# esp32Layout1.net
KiCad netlist of a schematic drawn in EAGLE
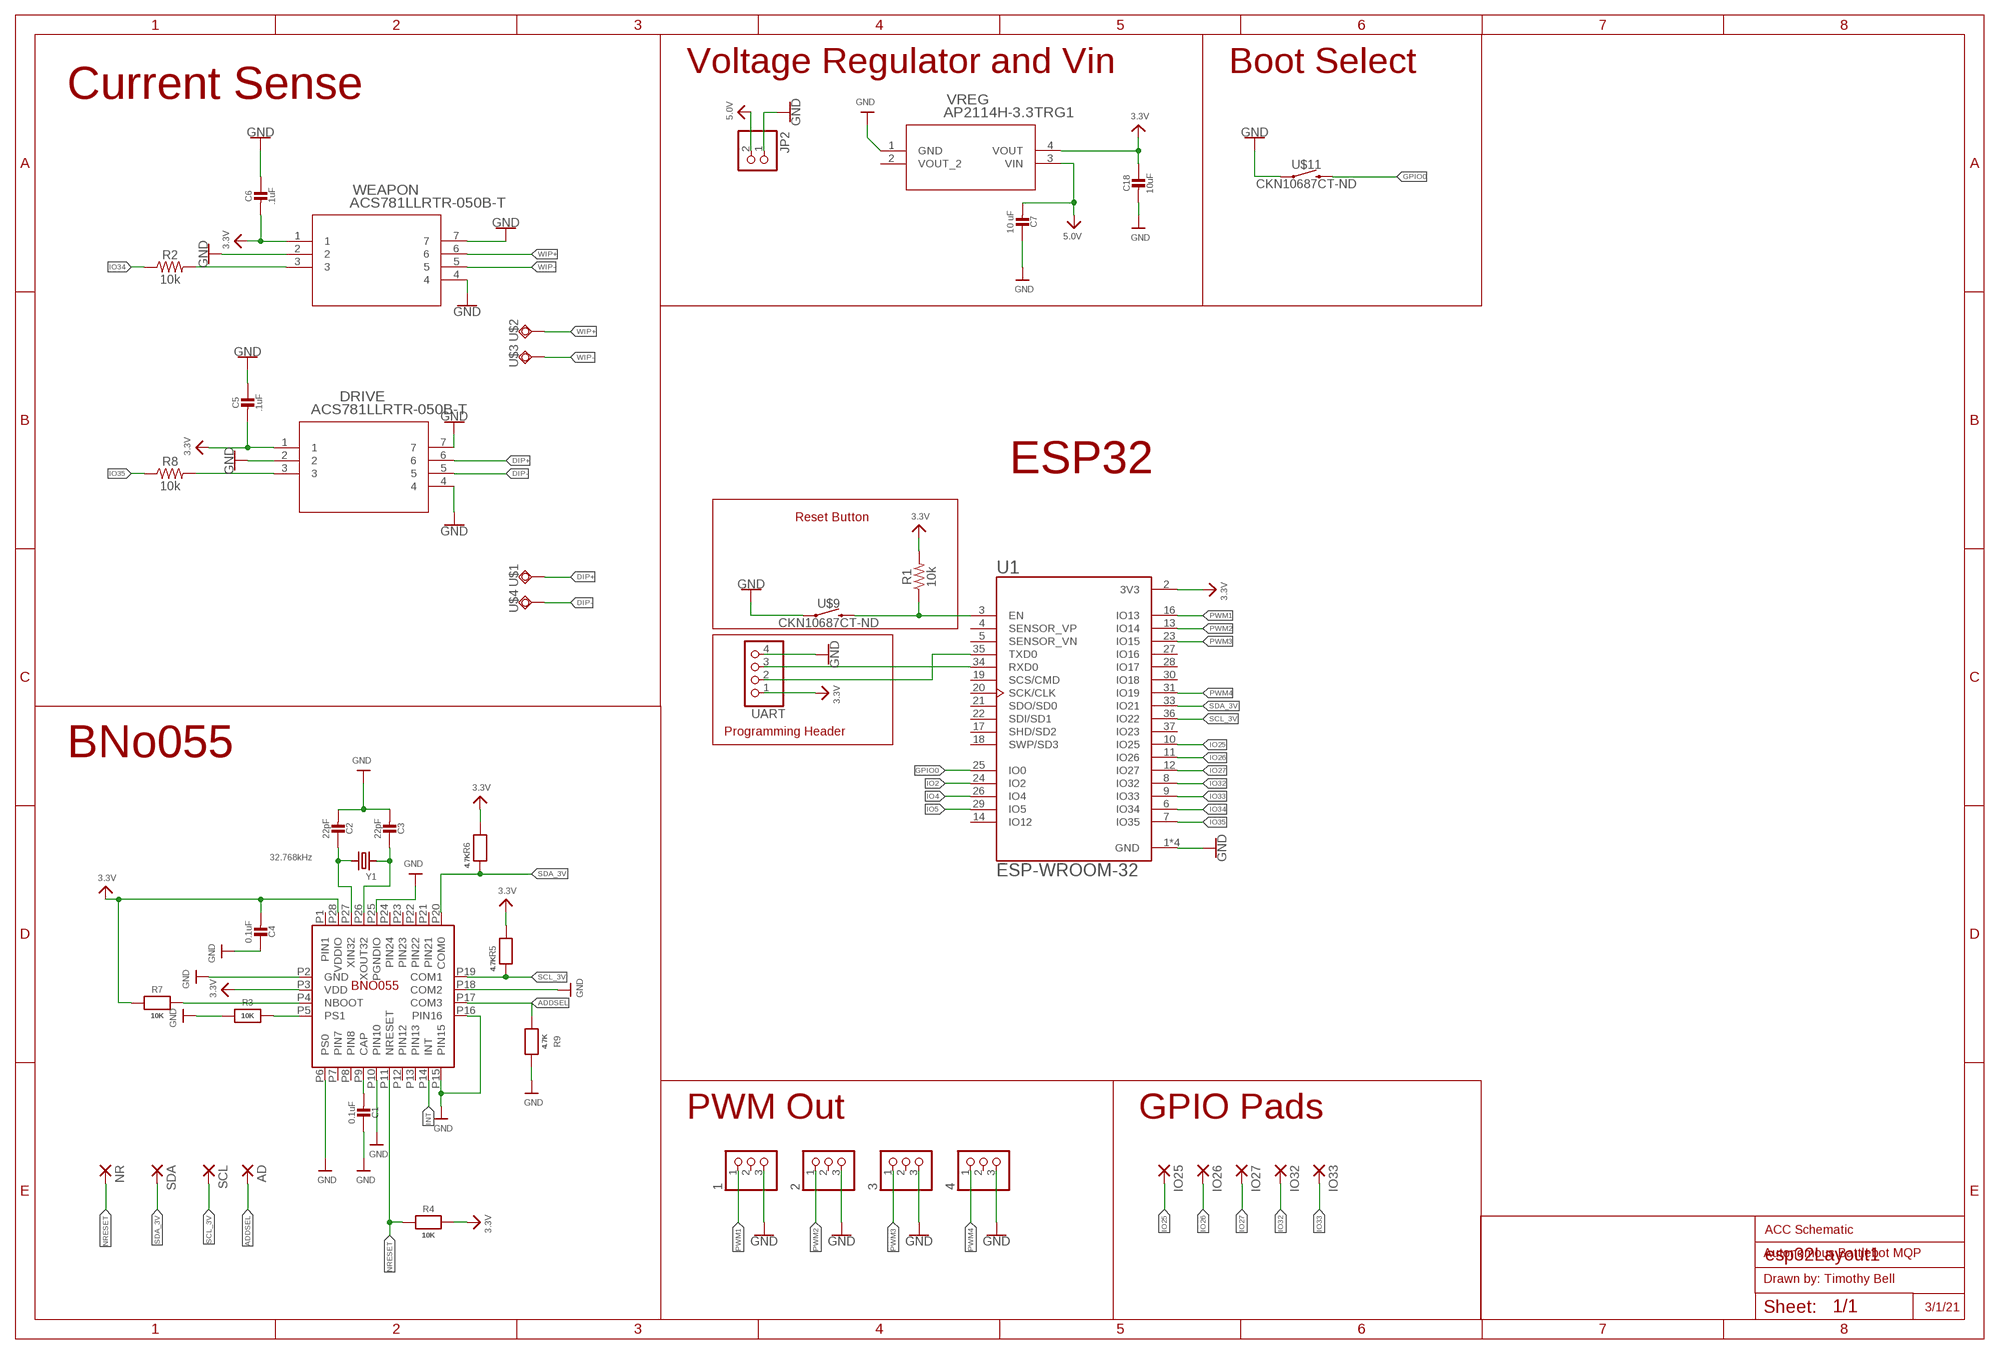
[diagram p0: schematic, sheet 1]

(export (version "E")
  (design (tool "Eeschema 10.0.6"))
  (components
    (comp (ref "1")
      (value "PINHD-1X3")
      (footprint "eagle-import:1X03")
      (libsource (lib "eagle-import") (part "PINHD-1X3"))
    )
    (comp (ref "2")
      (value "PINHD-1X3")
      (footprint "eagle-import:1X03")
      (libsource (lib "eagle-import") (part "PINHD-1X3"))
    )
    (comp (ref "3")
      (value "PINHD-1X3")
      (footprint "eagle-import:1X03")
      (libsource (lib "eagle-import") (part "PINHD-1X3"))
    )
    (comp (ref "4")
      (value "PINHD-1X3")
      (footprint "eagle-import:1X03")
      (libsource (lib "eagle-import") (part "PINHD-1X3"))
    )
    (comp (ref "AD")
      (value "SMD2")
      (footprint "eagle-import:SMD1,27-2,54")
      (libsource (lib "eagle-import") (part "SMD2"))
    )
    (comp (ref "BNO055")
      (value "BNO055")
      (footprint "eagle-import:BNO055")
      (libsource (lib "eagle-import") (part "BNO055"))
    )
    (comp (ref "C1")
      (value "0.1uF")
      (footprint "eagle-import:0805-NO")
      (libsource (lib "eagle-import") (part "CAP_CERAMIC0805-NOOUTLINE"))
    )
    (comp (ref "C2")
      (value "22pF")
      (footprint "eagle-import:0805-NO")
      (libsource (lib "eagle-import") (part "CAP_CERAMIC0805-NOOUTLINE"))
    )
    (comp (ref "C3")
      (value "22pF")
      (footprint "eagle-import:0805-NO")
      (libsource (lib "eagle-import") (part "CAP_CERAMIC0805-NOOUTLINE"))
    )
    (comp (ref "C4")
      (value "0.1uF")
      (footprint "eagle-import:0805-NO")
      (libsource (lib "eagle-import") (part "CAP_CERAMIC0805-NOOUTLINE"))
    )
    (comp (ref "C5")
      (value ".1uF")
      (footprint "eagle-import:0805_10MGAP")
      (libsource (lib "eagle-import") (part "CAP_CERAMIC0805_10MGAP"))
    )
    (comp (ref "C6")
      (value ".1uF")
      (footprint "eagle-import:0805_10MGAP")
      (libsource (lib "eagle-import") (part "CAP_CERAMIC0805_10MGAP"))
    )
    (comp (ref "C7")
      (value "10 uF")
      (footprint "eagle-import:0805-NO")
      (libsource (lib "eagle-import") (part "CAP_CERAMIC0805-NOOUTLINE"))
    )
    (comp (ref "C18")
      (value "10uF")
      (footprint "eagle-import:0805_10MGAP")
      (libsource (lib "eagle-import") (part "CAP_CERAMIC0805_10MGAP"))
    )
    (comp (ref "DRIVE")
      (value "ACS781LLRTR-050B-T")
      (footprint "eagle-import:PSOF7_ACS781LLRTR-050B-T_ALM")
      (fields (field (name "COPYRIGHT") "Copyright (C) 2018 Accelerated Designs. All rights reserved"))
      (libsource (lib "eagle-import") (part "ACS781LLRTR-050B-T"))
    )
    (comp (ref "IO25")
      (value "SMD2")
      (footprint "eagle-import:SMD1,27-2,54")
      (libsource (lib "eagle-import") (part "SMD2"))
    )
    (comp (ref "IO26")
      (value "SMD2")
      (footprint "eagle-import:SMD1,27-2,54")
      (libsource (lib "eagle-import") (part "SMD2"))
    )
    (comp (ref "IO27")
      (value "SMD2")
      (footprint "eagle-import:SMD1,27-2,54")
      (libsource (lib "eagle-import") (part "SMD2"))
    )
    (comp (ref "IO32")
      (value "SMD2")
      (footprint "eagle-import:SMD1,27-2,54")
      (libsource (lib "eagle-import") (part "SMD2"))
    )
    (comp (ref "IO33")
      (value "SMD2")
      (footprint "eagle-import:SMD1,27-2,54")
      (libsource (lib "eagle-import") (part "SMD2"))
    )
    (comp (ref "JP2")
      (value "PINHD-1X2")
      (footprint "eagle-import:1X02")
      (libsource (lib "eagle-import") (part "PINHD-1X2"))
    )
    (comp (ref "NR")
      (value "SMD2")
      (footprint "eagle-import:SMD1,27-2,54")
      (libsource (lib "eagle-import") (part "SMD2"))
    )
    (comp (ref "R1")
      (value "10k")
      (footprint "eagle-import:0603")
      (libsource (lib "eagle-import") (part "10KOHM-0603-1/10W-1%"))
    )
    (comp (ref "R2")
      (value "10k")
      (footprint "eagle-import:0603")
      (libsource (lib "eagle-import") (part "10KOHM-0603-1/10W-1%"))
    )
    (comp (ref "R3")
      (value "10K")
      (footprint "eagle-import:0805-NO")
      (libsource (lib "eagle-import") (part "RESISTOR0805_NOOUTLINE"))
    )
    (comp (ref "R4")
      (value "10K")
      (footprint "eagle-import:0805-NO")
      (libsource (lib "eagle-import") (part "RESISTOR0805_NOOUTLINE"))
    )
    (comp (ref "R5")
      (value "4.7K")
      (footprint "eagle-import:0805-NO")
      (libsource (lib "eagle-import") (part "RESISTOR0805_NOOUTLINE"))
    )
    (comp (ref "R6")
      (value "4.7K")
      (footprint "eagle-import:0805-NO")
      (libsource (lib "eagle-import") (part "RESISTOR0805_NOOUTLINE"))
    )
    (comp (ref "R7")
      (value "10K")
      (footprint "eagle-import:0805-NO")
      (libsource (lib "eagle-import") (part "RESISTOR0805_NOOUTLINE"))
    )
    (comp (ref "R8")
      (value "10k")
      (footprint "eagle-import:0603")
      (libsource (lib "eagle-import") (part "10KOHM-0603-1/10W-1%"))
    )
    (comp (ref "R9")
      (value "4.7K")
      (footprint "eagle-import:0805-NO")
      (libsource (lib "eagle-import") (part "RESISTOR0805_NOOUTLINE"))
    )
    (comp (ref "SCL")
      (value "SMD2")
      (footprint "eagle-import:SMD1,27-2,54")
      (libsource (lib "eagle-import") (part "SMD2"))
    )
    (comp (ref "SDA")
      (value "SMD2")
      (footprint "eagle-import:SMD1,27-2,54")
      (libsource (lib "eagle-import") (part "SMD2"))
    )
    (comp (ref "U$1")
      (value "HCURR_PAD")
      (footprint "eagle-import:HCURR_PAD")
      (libsource (lib "eagle-import") (part "HCURR_PAD"))
    )
    (comp (ref "U$2")
      (value "HCURR_PAD")
      (footprint "eagle-import:HCURR_PAD")
      (libsource (lib "eagle-import") (part "HCURR_PAD"))
    )
    (comp (ref "U$3")
      (value "HCURR_PAD")
      (footprint "eagle-import:HCURR_PAD")
      (libsource (lib "eagle-import") (part "HCURR_PAD"))
    )
    (comp (ref "U$4")
      (value "HCURR_PAD")
      (footprint "eagle-import:HCURR_PAD")
      (libsource (lib "eagle-import") (part "HCURR_PAD"))
    )
    (comp (ref "U$9")
      (value "CKN10687CT-ND")
      (footprint "eagle-import:CKN10687CT-ND")
      (libsource (lib "eagle-import") (part "CKN10687CT-ND"))
    )
    (comp (ref "U$11")
      (value "CKN10687CT-ND")
      (footprint "eagle-import:CKN10687CT-ND")
      (libsource (lib "eagle-import") (part "CKN10687CT-ND"))
    )
    (comp (ref "U1")
      (value "ESP-WROOM-32")
      (footprint "eagle-import:MODULE_ESP-WROOM-32")
      (fields (field (name "MF") "Olimex LTD"))
      (libsource (lib "eagle-import") (part "ESP-WROOM-32"))
    )
    (comp (ref "UART")
      (value "PINHD-1X4")
      (footprint "eagle-import:1X04")
      (libsource (lib "eagle-import") (part "PINHD-1X4"))
    )
    (comp (ref "VREG")
      (value "AP2114H-3.3TRG1")
      (footprint "eagle-import:SOT-223_DIO")
      (libsource (lib "eagle-import") (part "AP2114H-3.3TRG1"))
    )
    (comp (ref "WEAPON")
      (value "ACS781LLRTR-050B-T")
      (footprint "eagle-import:PSOF7_ACS781LLRTR-050B-T_ALM")
      (fields (field (name "COPYRIGHT") "Copyright (C) 2018 Accelerated Designs. All rights reserved"))
      (libsource (lib "eagle-import") (part "ACS781LLRTR-050B-T"))
    )
    (comp (ref "Y1")
      (value "32.768kHz")
      (footprint "eagle-import:CRYSTAL_8X3.8")
      (libsource (lib "eagle-import") (part "CRYSTAL8.0X3.8"))
    )
  )
  (nets
    (net (code "1") (name "3.3V") (class "Default")
      (node (ref "BNO055") (pin "P28") (pinfunction "VDDIO_P28") (pintype "bidirectional"))
      (node (ref "BNO055") (pin "P3") (pinfunction "VDD_P3") (pintype "bidirectional"))
      (node (ref "C18") (pin "1") (pinfunction "1_1") (pintype "passive"))
      (node (ref "C4") (pin "2") (pinfunction "2_2") (pintype "passive"))
      (node (ref "C5") (pin "2") (pinfunction "2_2") (pintype "passive"))
      (node (ref "C6") (pin "2") (pinfunction "2_2") (pintype "passive"))
      (node (ref "DRIVE") (pin "1") (pinfunction "1_1") (pintype "passive"))
      (node (ref "R1") (pin "2") (pinfunction "2_2") (pintype "passive"))
      (node (ref "R4") (pin "2") (pinfunction "2_2") (pintype "passive"))
      (node (ref "R5") (pin "2") (pinfunction "2_2") (pintype "passive"))
      (node (ref "R6") (pin "2") (pinfunction "2_2") (pintype "passive"))
      (node (ref "R7") (pin "1") (pinfunction "1_1") (pintype "passive"))
      (node (ref "U1") (pin "2") (pinfunction "3V3_2") (pintype "power_in"))
      (node (ref "UART") (pin "1") (pinfunction "1_1") (pintype "passive"))
      (node (ref "VREG") (pin "4") (pinfunction "VOUT_4") (pintype "output"))
      (node (ref "WEAPON") (pin "1") (pinfunction "1_1") (pintype "passive"))
    )
    (net (code "2") (name "5.0V") (class "Default")
      (node (ref "C7") (pin "2") (pinfunction "2_2") (pintype "passive"))
      (node (ref "JP2") (pin "2") (pinfunction "2_2") (pintype "passive"))
      (node (ref "VREG") (pin "3") (pinfunction "VIN_3") (pintype "input"))
    )
    (net (code "3") (name "ADDSEL") (class "Default")
      (node (ref "AD") (pin "1") (pinfunction "P_1") (pintype "passive"))
      (node (ref "BNO055") (pin "P17") (pinfunction "COM3_P17") (pintype "bidirectional"))
      (node (ref "R9") (pin "1") (pinfunction "1_1") (pintype "passive"))
    )
    (net (code "4") (name "DIP+") (class "Default")
      (node (ref "DRIVE") (pin "6") (pinfunction "6_6") (pintype "passive"))
      (node (ref "U$1") (pin "P$1") (pinfunction "TP_P$1") (pintype "input"))
    )
    (net (code "5") (name "DIP-") (class "Default")
      (node (ref "DRIVE") (pin "5") (pinfunction "5_5") (pintype "passive"))
      (node (ref "U$4") (pin "P$1") (pinfunction "TP_P$1") (pintype "input"))
    )
    (net (code "6") (name "GND") (class "Default")
      (node (ref "1") (pin "3") (pinfunction "3_3") (pintype "passive"))
      (node (ref "2") (pin "3") (pinfunction "3_3") (pintype "passive"))
      (node (ref "3") (pin "3") (pinfunction "3_3") (pintype "passive"))
      (node (ref "4") (pin "3") (pinfunction "3_3") (pintype "passive"))
      (node (ref "BNO055") (pin "P10") (pinfunction "PIN10_P10") (pintype "bidirectional"))
      (node (ref "BNO055") (pin "P15") (pinfunction "PIN15_P15") (pintype "bidirectional"))
      (node (ref "BNO055") (pin "P16") (pinfunction "PIN16_P16") (pintype "bidirectional"))
      (node (ref "BNO055") (pin "P18") (pinfunction "COM2_P18") (pintype "bidirectional"))
      (node (ref "BNO055") (pin "P2") (pinfunction "GND_P2") (pintype "bidirectional"))
      (node (ref "BNO055") (pin "P25") (pinfunction "PGNDIO_P25") (pintype "bidirectional"))
      (node (ref "BNO055") (pin "P6") (pinfunction "PS0_P6") (pintype "bidirectional"))
      (node (ref "C1") (pin "1") (pinfunction "1_1") (pintype "passive"))
      (node (ref "C18") (pin "2") (pinfunction "2_2") (pintype "passive"))
      (node (ref "C2") (pin "2") (pinfunction "2_2") (pintype "passive"))
      (node (ref "C3") (pin "2") (pinfunction "2_2") (pintype "passive"))
      (node (ref "C4") (pin "1") (pinfunction "1_1") (pintype "passive"))
      (node (ref "C5") (pin "1") (pinfunction "1_1") (pintype "passive"))
      (node (ref "C6") (pin "1") (pinfunction "1_1") (pintype "passive"))
      (node (ref "C7") (pin "1") (pinfunction "1_1") (pintype "passive"))
      (node (ref "DRIVE") (pin "2") (pinfunction "2_2") (pintype "passive"))
      (node (ref "DRIVE") (pin "4") (pinfunction "4_4") (pintype "passive"))
      (node (ref "DRIVE") (pin "7") (pinfunction "7_7") (pintype "passive"))
      (node (ref "JP2") (pin "1") (pinfunction "1_1") (pintype "passive"))
      (node (ref "R3") (pin "1") (pinfunction "1_1") (pintype "passive"))
      (node (ref "R9") (pin "2") (pinfunction "2_2") (pintype "passive"))
      (node (ref "U$11") (pin "P$1") (pinfunction "1_P$1") (pintype "passive"))
      (node (ref "U$11") (pin "P$2") (pinfunction "1_P$2") (pintype "passive"))
      (node (ref "U$9") (pin "P$1") (pinfunction "1_P$1") (pintype "passive"))
      (node (ref "U$9") (pin "P$2") (pinfunction "1_P$2") (pintype "passive"))
      (node (ref "U1") (pin "1") (pinfunction "GND_1") (pintype "power_in"))
      (node (ref "U1") (pin "1.1") (pinfunction "GND_1.1") (pintype "power_in"))
      (node (ref "U1") (pin "15") (pinfunction "GND_15") (pintype "power_in"))
      (node (ref "U1") (pin "38") (pinfunction "GND_38") (pintype "power_in"))
      (node (ref "UART") (pin "4") (pinfunction "4_4") (pintype "passive"))
      (node (ref "VREG") (pin "1") (pinfunction "GND_1") (pintype "passive"))
      (node (ref "WEAPON") (pin "2") (pinfunction "2_2") (pintype "passive"))
      (node (ref "WEAPON") (pin "4") (pinfunction "4_4") (pintype "passive"))
      (node (ref "WEAPON") (pin "7") (pinfunction "7_7") (pintype "passive"))
    )
    (net (code "7") (name "GPIO0") (class "Default")
      (node (ref "U$11") (pin "P$3") (pinfunction "2_P$3") (pintype "passive"))
      (node (ref "U$11") (pin "P$4") (pinfunction "2_P$4") (pintype "passive"))
      (node (ref "U1") (pin "25") (pinfunction "IO0_25") (pintype "bidirectional"))
    )
    (net (code "8") (name "INT") (class "Default")
      (node (ref "BNO055") (pin "P14") (pinfunction "INT_P14") (pintype "bidirectional"))
    )
    (net (code "9") (name "IO2") (class "Default")
      (node (ref "U1") (pin "24") (pinfunction "IO2_24") (pintype "bidirectional"))
    )
    (net (code "10") (name "IO4") (class "Default")
      (node (ref "U1") (pin "26") (pinfunction "IO4_26") (pintype "bidirectional"))
    )
    (net (code "11") (name "IO5") (class "Default")
      (node (ref "U1") (pin "29") (pinfunction "IO5_29") (pintype "bidirectional"))
    )
    (net (code "12") (name "IO25") (class "Default")
      (node (ref "IO25") (pin "1") (pinfunction "P_1") (pintype "passive"))
      (node (ref "U1") (pin "10") (pinfunction "IO25_10") (pintype "bidirectional"))
    )
    (net (code "13") (name "IO26") (class "Default")
      (node (ref "IO26") (pin "1") (pinfunction "P_1") (pintype "passive"))
      (node (ref "U1") (pin "11") (pinfunction "IO26_11") (pintype "bidirectional"))
    )
    (net (code "14") (name "IO27") (class "Default")
      (node (ref "IO27") (pin "1") (pinfunction "P_1") (pintype "passive"))
      (node (ref "U1") (pin "12") (pinfunction "IO27_12") (pintype "bidirectional"))
    )
    (net (code "15") (name "IO32") (class "Default")
      (node (ref "IO32") (pin "1") (pinfunction "P_1") (pintype "passive"))
      (node (ref "U1") (pin "8") (pinfunction "IO32_8") (pintype "bidirectional"))
    )
    (net (code "16") (name "IO33") (class "Default")
      (node (ref "IO33") (pin "1") (pinfunction "P_1") (pintype "passive"))
      (node (ref "U1") (pin "9") (pinfunction "IO33_9") (pintype "bidirectional"))
    )
    (net (code "17") (name "IO34") (class "Default")
      (node (ref "R2") (pin "1") (pinfunction "1_1") (pintype "passive"))
      (node (ref "U1") (pin "6") (pinfunction "IO34_6") (pintype "bidirectional"))
    )
    (net (code "18") (name "IO35") (class "Default")
      (node (ref "R8") (pin "1") (pinfunction "1_1") (pintype "passive"))
      (node (ref "U1") (pin "7") (pinfunction "IO35_7") (pintype "bidirectional"))
    )
    (net (code "19") (name "NRESET") (class "Default")
      (node (ref "BNO055") (pin "P11") (pinfunction "NRESET_P11") (pintype "bidirectional"))
      (node (ref "NR") (pin "1") (pinfunction "P_1") (pintype "passive"))
      (node (ref "R4") (pin "1") (pinfunction "1_1") (pintype "passive"))
    )
    (net (code "20") (name "Net-(BNO055-CAP)") (class "Default")
      (node (ref "BNO055") (pin "P9") (pinfunction "CAP_P9") (pintype "bidirectional"))
      (node (ref "C1") (pin "2") (pinfunction "2_2") (pintype "passive"))
    )
    (net (code "21") (name "Net-(BNO055-NBOOT)") (class "Default")
      (node (ref "BNO055") (pin "P4") (pinfunction "NBOOT_P4") (pintype "bidirectional"))
      (node (ref "R7") (pin "2") (pinfunction "2_2") (pintype "passive"))
    )
    (net (code "22") (name "Net-(BNO055-PS1)") (class "Default")
      (node (ref "BNO055") (pin "P5") (pinfunction "PS1_P5") (pintype "bidirectional"))
      (node (ref "R3") (pin "2") (pinfunction "2_2") (pintype "passive"))
    )
    (net (code "23") (name "Net-(BNO055-XIN32)") (class "Default")
      (node (ref "BNO055") (pin "P27") (pinfunction "XIN32_P27") (pintype "bidirectional"))
      (node (ref "C2") (pin "1") (pinfunction "1_1") (pintype "passive"))
      (node (ref "Y1") (pin "P$4") (pinfunction "2_P$4") (pintype "passive"))
    )
    (net (code "24") (name "Net-(BNO055-XOUT32)") (class "Default")
      (node (ref "BNO055") (pin "P26") (pinfunction "XOUT32_P26") (pintype "bidirectional"))
      (node (ref "C3") (pin "1") (pinfunction "1_1") (pintype "passive"))
      (node (ref "Y1") (pin "P$1") (pinfunction "1_P$1") (pintype "passive"))
    )
    (net (code "25") (name "Net-(DRIVE-Pad3)") (class "Default")
      (node (ref "DRIVE") (pin "3") (pinfunction "3_3") (pintype "passive"))
      (node (ref "R8") (pin "2") (pinfunction "2_2") (pintype "passive"))
    )
    (net (code "26") (name "Net-(R2-Pad2)") (class "Default")
      (node (ref "R2") (pin "2") (pinfunction "2_2") (pintype "passive"))
      (node (ref "WEAPON") (pin "3") (pinfunction "3_3") (pintype "passive"))
    )
    (net (code "27") (name "Net-(U1-EN)") (class "Default")
      (node (ref "R1") (pin "1") (pinfunction "1_1") (pintype "passive"))
      (node (ref "U$9") (pin "P$3") (pinfunction "2_P$3") (pintype "passive"))
      (node (ref "U$9") (pin "P$4") (pinfunction "2_P$4") (pintype "passive"))
      (node (ref "U1") (pin "3") (pinfunction "EN_3") (pintype "input"))
    )
    (net (code "28") (name "Net-(U1-RXD0)") (class "Default")
      (node (ref "U1") (pin "34") (pinfunction "RXD0_34") (pintype "bidirectional"))
      (node (ref "UART") (pin "3") (pinfunction "3_3") (pintype "passive"))
    )
    (net (code "29") (name "Net-(U1-TXD0)") (class "Default")
      (node (ref "U1") (pin "35") (pinfunction "TXD0_35") (pintype "bidirectional"))
      (node (ref "UART") (pin "2") (pinfunction "2_2") (pintype "passive"))
    )
    (net (code "30") (name "PWM1") (class "Default")
      (node (ref "1") (pin "1") (pinfunction "1_1") (pintype "passive"))
      (node (ref "U1") (pin "16") (pinfunction "IO13_16") (pintype "bidirectional"))
    )
    (net (code "31") (name "PWM2") (class "Default")
      (node (ref "2") (pin "1") (pinfunction "1_1") (pintype "passive"))
      (node (ref "U1") (pin "13") (pinfunction "IO14_13") (pintype "bidirectional"))
    )
    (net (code "32") (name "PWM3") (class "Default")
      (node (ref "3") (pin "1") (pinfunction "1_1") (pintype "passive"))
      (node (ref "U1") (pin "23") (pinfunction "IO15_23") (pintype "bidirectional"))
    )
    (net (code "33") (name "PWM4") (class "Default")
      (node (ref "4") (pin "1") (pinfunction "1_1") (pintype "passive"))
      (node (ref "U1") (pin "31") (pinfunction "IO19_31") (pintype "bidirectional"))
    )
    (net (code "34") (name "SCL_3V") (class "Default")
      (node (ref "BNO055") (pin "P19") (pinfunction "COM1_P19") (pintype "bidirectional"))
      (node (ref "R5") (pin "1") (pinfunction "1_1") (pintype "passive"))
      (node (ref "SCL") (pin "1") (pinfunction "P_1") (pintype "passive"))
      (node (ref "U1") (pin "36") (pinfunction "IO22_36") (pintype "bidirectional"))
    )
    (net (code "35") (name "SDA_3V") (class "Default")
      (node (ref "BNO055") (pin "P20") (pinfunction "COM0_P20") (pintype "bidirectional"))
      (node (ref "R6") (pin "1") (pinfunction "1_1") (pintype "passive"))
      (node (ref "SDA") (pin "1") (pinfunction "P_1") (pintype "passive"))
      (node (ref "U1") (pin "33") (pinfunction "IO21_33") (pintype "bidirectional"))
    )
    (net (code "36") (name "WIP+") (class "Default")
      (node (ref "U$2") (pin "P$1") (pinfunction "TP_P$1") (pintype "input"))
      (node (ref "WEAPON") (pin "6") (pinfunction "6_6") (pintype "passive"))
    )
    (net (code "37") (name "WIP-") (class "Default")
      (node (ref "U$3") (pin "P$1") (pinfunction "TP_P$1") (pintype "input"))
      (node (ref "WEAPON") (pin "5") (pinfunction "5_5") (pintype "passive"))
    )
    (net (code "38") (name "unconnected-(1-Pad2)") (class "Default")
      (node (ref "1") (pin "2") (pinfunction "2_2") (pintype "passive"))
    )
    (net (code "39") (name "unconnected-(2-Pad2)") (class "Default")
      (node (ref "2") (pin "2") (pinfunction "2_2") (pintype "passive"))
    )
    (net (code "40") (name "unconnected-(3-Pad2)") (class "Default")
      (node (ref "3") (pin "2") (pinfunction "2_2") (pintype "passive"))
    )
    (net (code "41") (name "unconnected-(4-Pad2)") (class "Default")
      (node (ref "4") (pin "2") (pinfunction "2_2") (pintype "passive"))
    )
    (net (code "42") (name "unconnected-(BNO055-PIN1-PadP1)") (class "Default")
      (node (ref "BNO055") (pin "P1") (pinfunction "PIN1_P1") (pintype "bidirectional"))
    )
    (net (code "43") (name "unconnected-(BNO055-PIN7-PadP7)") (class "Default")
      (node (ref "BNO055") (pin "P7") (pinfunction "PIN7_P7") (pintype "bidirectional"))
    )
    (net (code "44") (name "unconnected-(BNO055-PIN8-PadP8)") (class "Default")
      (node (ref "BNO055") (pin "P8") (pinfunction "PIN8_P8") (pintype "bidirectional"))
    )
    (net (code "45") (name "unconnected-(BNO055-PIN12-PadP12)") (class "Default")
      (node (ref "BNO055") (pin "P12") (pinfunction "PIN12_P12") (pintype "bidirectional"))
    )
    (net (code "46") (name "unconnected-(BNO055-PIN13-PadP13)") (class "Default")
      (node (ref "BNO055") (pin "P13") (pinfunction "PIN13_P13") (pintype "bidirectional"))
    )
    (net (code "47") (name "unconnected-(BNO055-PIN21-PadP21)") (class "Default")
      (node (ref "BNO055") (pin "P21") (pinfunction "PIN21_P21") (pintype "bidirectional"))
    )
    (net (code "48") (name "unconnected-(BNO055-PIN22-PadP22)") (class "Default")
      (node (ref "BNO055") (pin "P22") (pinfunction "PIN22_P22") (pintype "bidirectional"))
    )
    (net (code "49") (name "unconnected-(BNO055-PIN23-PadP23)") (class "Default")
      (node (ref "BNO055") (pin "P23") (pinfunction "PIN23_P23") (pintype "bidirectional"))
    )
    (net (code "50") (name "unconnected-(BNO055-PIN24-PadP24)") (class "Default")
      (node (ref "BNO055") (pin "P24") (pinfunction "PIN24_P24") (pintype "bidirectional"))
    )
    (net (code "51") (name "unconnected-(U1-IO12-Pad14)") (class "Default")
      (node (ref "U1") (pin "14") (pinfunction "IO12_14") (pintype "bidirectional"))
    )
    (net (code "52") (name "unconnected-(U1-IO16-Pad27)") (class "Default")
      (node (ref "U1") (pin "27") (pinfunction "IO16_27") (pintype "bidirectional"))
    )
    (net (code "53") (name "unconnected-(U1-IO17-Pad28)") (class "Default")
      (node (ref "U1") (pin "28") (pinfunction "IO17_28") (pintype "bidirectional"))
    )
    (net (code "54") (name "unconnected-(U1-IO18-Pad30)") (class "Default")
      (node (ref "U1") (pin "30") (pinfunction "IO18_30") (pintype "bidirectional"))
    )
    (net (code "55") (name "unconnected-(U1-IO23-Pad37)") (class "Default")
      (node (ref "U1") (pin "37") (pinfunction "IO23_37") (pintype "bidirectional"))
    )
    (net (code "56") (name "unconnected-(U1-SCK{slash}CLK-Pad20)") (class "Default")
      (node (ref "U1") (pin "20") (pinfunction "SCK/CLK_20") (pintype "bidirectional"))
    )
    (net (code "57") (name "unconnected-(U1-SCS{slash}CMD-Pad19)") (class "Default")
      (node (ref "U1") (pin "19") (pinfunction "SCS/CMD_19") (pintype "bidirectional"))
    )
    (net (code "58") (name "unconnected-(U1-SDI{slash}SD1-Pad22)") (class "Default")
      (node (ref "U1") (pin "22") (pinfunction "SDI/SD1_22") (pintype "bidirectional"))
    )
    (net (code "59") (name "unconnected-(U1-SDO{slash}SD0-Pad21)") (class "Default")
      (node (ref "U1") (pin "21") (pinfunction "SDO/SD0_21") (pintype "bidirectional"))
    )
    (net (code "60") (name "unconnected-(U1-SENSOR_VN-Pad5)") (class "Default")
      (node (ref "U1") (pin "5") (pinfunction "SENSOR_VN_5") (pintype "input"))
    )
    (net (code "61") (name "unconnected-(U1-SENSOR_VP-Pad4)") (class "Default")
      (node (ref "U1") (pin "4") (pinfunction "SENSOR_VP_4") (pintype "input"))
    )
    (net (code "62") (name "unconnected-(U1-SHD{slash}SD2-Pad17)") (class "Default")
      (node (ref "U1") (pin "17") (pinfunction "SHD/SD2_17") (pintype "bidirectional"))
    )
    (net (code "63") (name "unconnected-(U1-SWP{slash}SD3-Pad18)") (class "Default")
      (node (ref "U1") (pin "18") (pinfunction "SWP/SD3_18") (pintype "bidirectional"))
    )
    (net (code "64") (name "unconnected-(VREG-VOUT_2-Pad2)") (class "Default")
      (node (ref "VREG") (pin "2") (pinfunction "VOUT_2_2") (pintype "output"))
    )
  )
)
